# coaster.net
KiCad netlist of a schematic drawn in Altium Designer
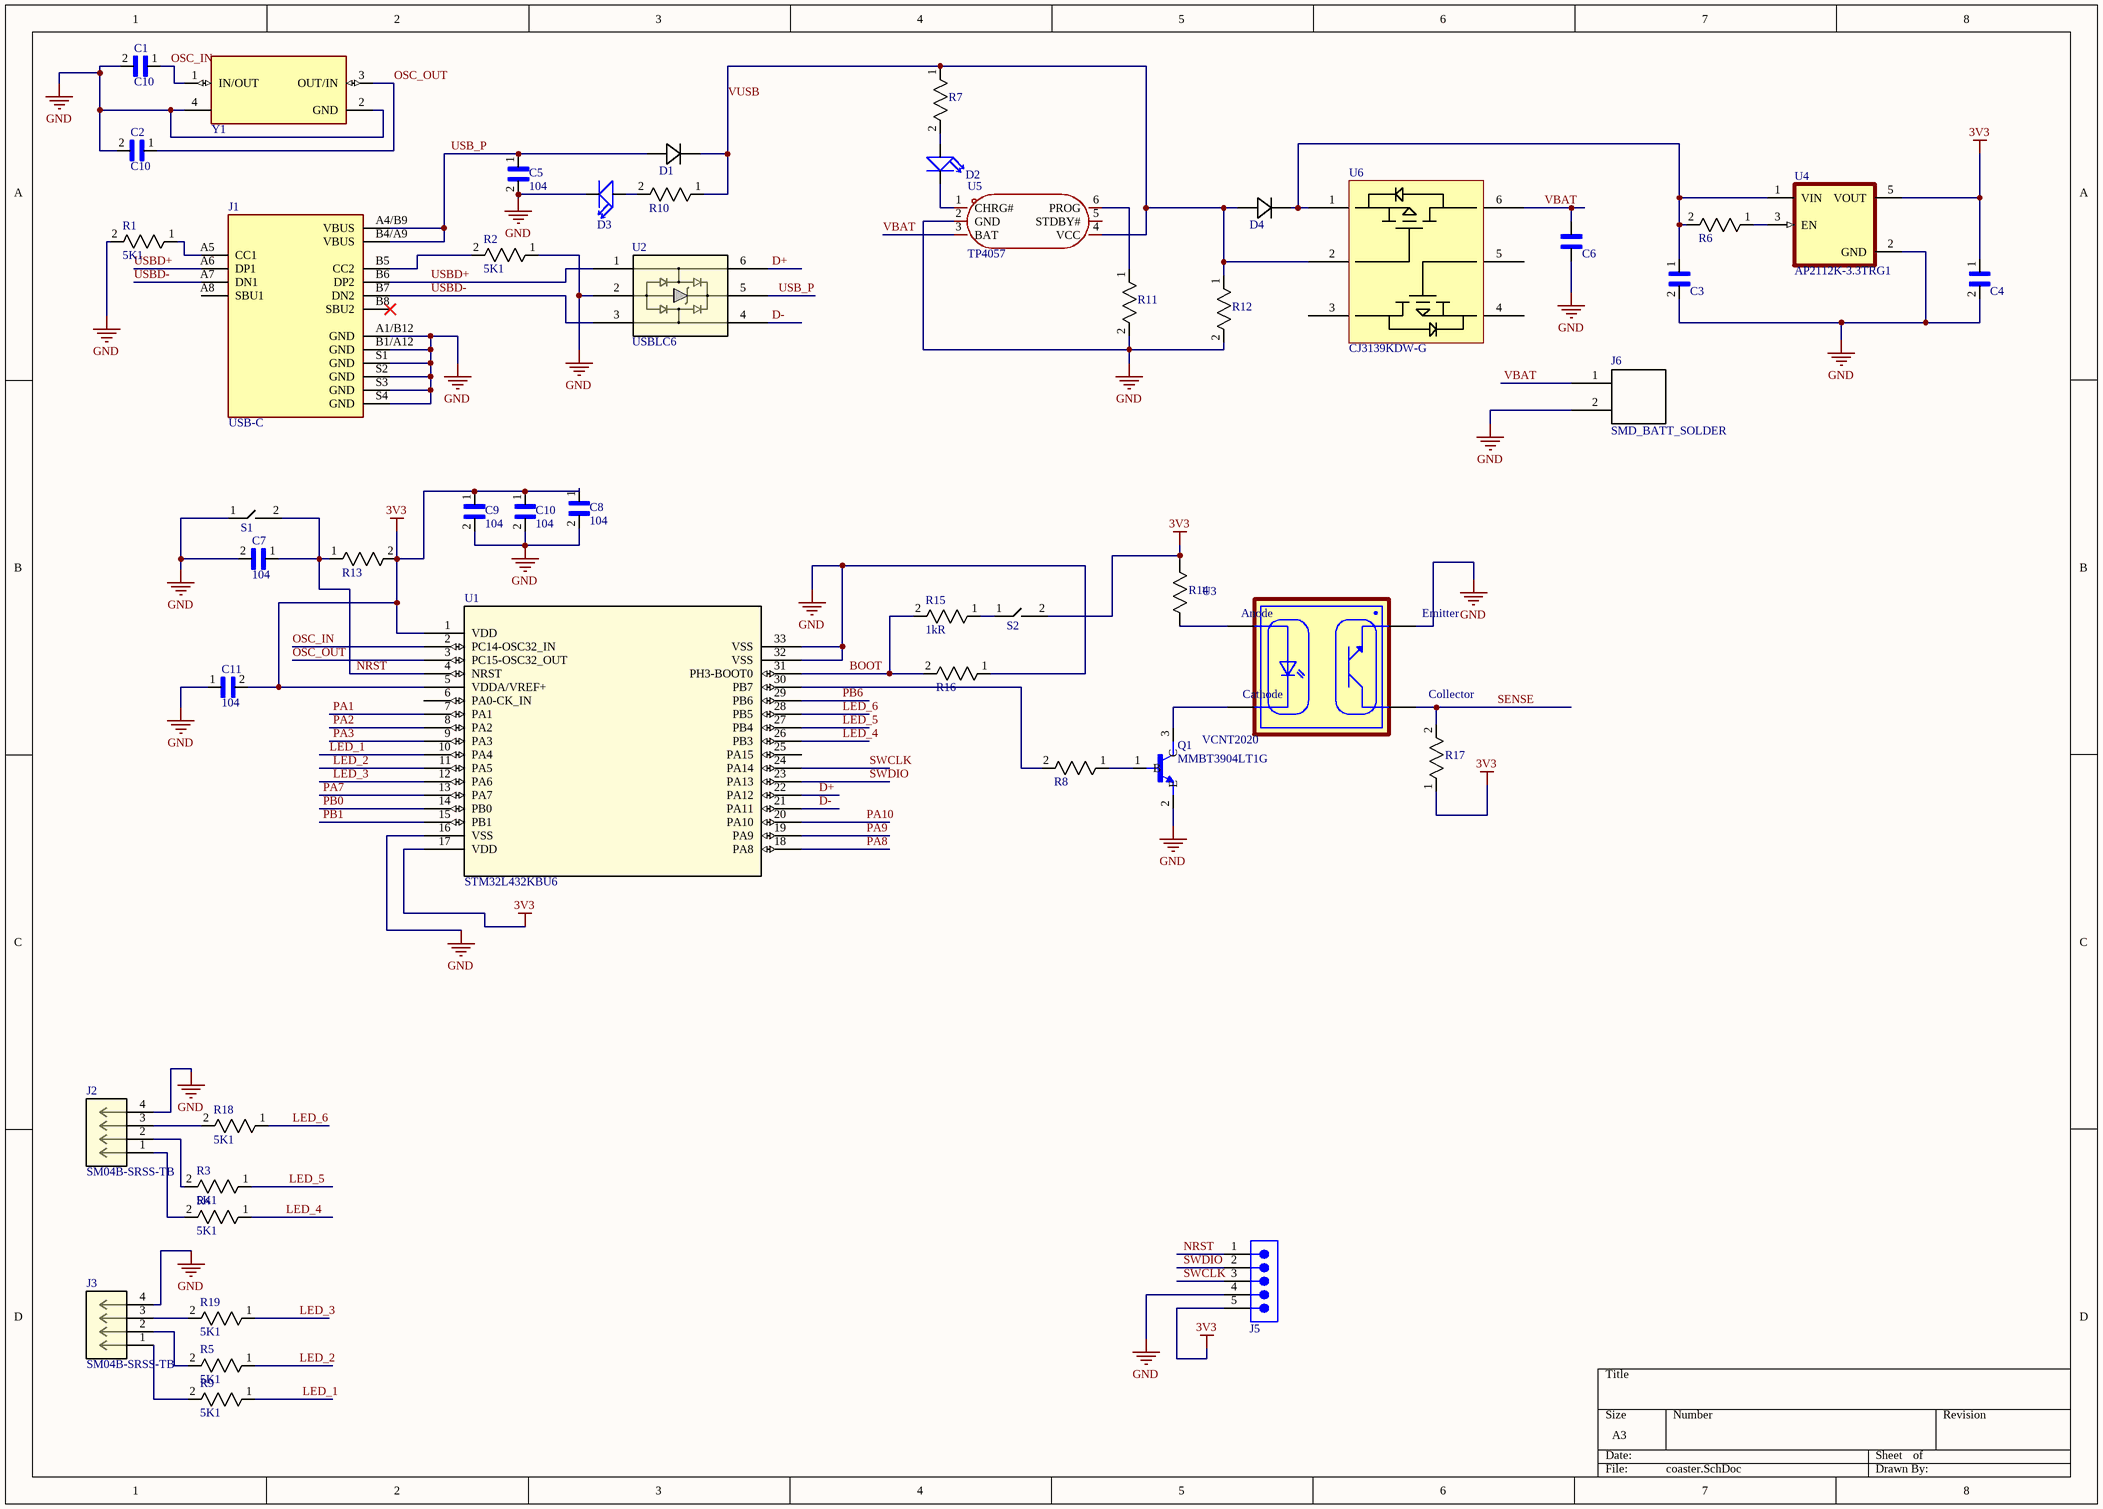
[diagram p0: coaster.SchDoc]

(export (version "E")
  (design (tool "Eeschema 10.0.6"))
  (components
    (comp (ref "C1")
      (value "C10")
      (footprint "RC0402")
      (description "0402 10 pF 50 V ±5 % Tolerance NP0 SMT Multilayer Ceramic Capacitor")
      (fields
        (field (name "MANUFACTURER") "Yageo")
        (field (name "MANUFACTURER PART NUMBER") "CC0402JRNPO9BN100")
      )
      (libsource (lib "Passive") (part "C10"))
    )
    (comp (ref "C2")
      (value "C10")
      (footprint "RC0402")
      (description "0402 10 pF 50 V ±5 % Tolerance NP0 SMT Multilayer Ceramic Capacitor")
      (fields
        (field (name "MANUFACTURER") "Yageo")
        (field (name "MANUFACTURER PART NUMBER") "CC0402JRNPO9BN100")
      )
      (libsource (lib "Passive") (part "C10"))
    )
    (comp (ref "C3")
      (value "CC0402KRX5R5BB105")
      (footprint "RC0402")
      (description "Multilayer Ceramic Capacitor, 1 uF, 100 V, ï¿½ 10%, X7R, 0402 [1005 Metric]")
      (fields (field (name "MANUFACTURER") "Yageo") (field (name "TOLERANCE") "10%"))
      (libsource (lib "imx8mnano") (part "C105"))
    )
    (comp (ref "C4")
      (value "CC0402KRX5R5BB105")
      (footprint "RC0402")
      (description "Multilayer Ceramic Capacitor, 1 uF, 100 V, ï¿½ 10%, X7R, 0402 [1005 Metric]")
      (fields (field (name "MANUFACTURER") "Yageo") (field (name "TOLERANCE") "10%"))
      (libsource (lib "imx8mnano") (part "C105"))
    )
    (comp (ref "C5")
      (value "104")
      (footprint "CAPC1005X55N2")
      (description "Multilayer Ceramic Capacitor, 0.1 uF, 16 V, ï¿½ 10%, X7R, 0402 [1005 Metric]")
      (fields
        (field (name "MANUFACTURER") "Yageo")
        (field (name "MANUFACTURER PART NUMBER") "CC0402KRX7R7BB104")
      )
      (libsource (lib "") (part "CC0402KRX7R7BB104_1"))
    )
    (comp (ref "C6")
      (value "CL21A106KOQNNNG")
      (footprint "CAPC2012X140N")
      (description "10 ÂµF Â±10% 16V Ceramic Capacitor X5R 0805 (2012 Metric)")
      (fields (field (name "MF") "Samsung Electro-Mechanics"))
      (libsource (lib "Passive") (part "10uF16v0805"))
    )
    (comp (ref "C7")
      (value "104")
      (footprint "CAPC1005X55N2")
      (description "Multilayer Ceramic Capacitor, 0.1 uF, 16 V, ï¿½ 10%, X7R, 0402 [1005 Metric]")
      (fields
        (field (name "MANUFACTURER") "Yageo")
        (field (name "MANUFACTURER PART NUMBER") "CC0402KRX7R7BB104")
      )
      (libsource (lib "Passive") (part "CC0402KRX7R7BB104"))
    )
    (comp (ref "C8")
      (value "104")
      (footprint "CAPC1005X55N2")
      (description "Multilayer Ceramic Capacitor, 0.1 uF, 16 V, ï¿½ 10%, X7R, 0402 [1005 Metric]")
      (fields
        (field (name "MANUFACTURER") "Yageo")
        (field (name "MANUFACTURER PART NUMBER") "CC0402KRX7R7BB104")
      )
      (libsource (lib "") (part "CC0402KRX7R7BB104_1"))
    )
    (comp (ref "C9")
      (value "104")
      (footprint "CAPC1005X55N2")
      (description "Multilayer Ceramic Capacitor, 0.1 uF, 16 V, ï¿½ 10%, X7R, 0402 [1005 Metric]")
      (fields
        (field (name "MANUFACTURER") "Yageo")
        (field (name "MANUFACTURER PART NUMBER") "CC0402KRX7R7BB104")
      )
      (libsource (lib "") (part "CC0402KRX7R7BB104_1"))
    )
    (comp (ref "C10")
      (value "104")
      (footprint "CAPC1005X55N2")
      (description "Multilayer Ceramic Capacitor, 0.1 uF, 16 V, ï¿½ 10%, X7R, 0402 [1005 Metric]")
      (fields
        (field (name "MANUFACTURER") "Yageo")
        (field (name "MANUFACTURER PART NUMBER") "CC0402KRX7R7BB104")
      )
      (libsource (lib "") (part "CC0402KRX7R7BB104_1"))
    )
    (comp (ref "C11")
      (value "104")
      (footprint "CAPC1005X55N2")
      (description "Multilayer Ceramic Capacitor, 0.1 uF, 16 V, ï¿½ 10%, X7R, 0402 [1005 Metric]")
      (fields
        (field (name "MANUFACTURER") "Yageo")
        (field (name "MANUFACTURER PART NUMBER") "CC0402KRX7R7BB104")
      )
      (libsource (lib "") (part "CC0402KRX7R7BB104_2"))
    )
    (comp (ref "D1")
      (value "SD103AWS-E3-08")
      (footprint "CR_WS-E3-08_VIS-L")
      (description "SCHOTTKY DIODE SOD323")
      (fields (field (name "COPYRIGHT") "Copyright (C) 2025 Ultra Librarian. All rights reserved."))
      (libsource (lib "Passive") (part "SD103AWS-E3-08"))
    )
    (comp (ref "D2")
      (value "LED")
      (footprint "LEDM1608X80")
      (description "Single Color LED, Ultra Bright Orange, Water Clear, 1.1mm")
      (fields
        (field (name "MANUFACTURER") "Vishay Lite-On")
        (field (name "MANUFACTURER PART NUMBER") "LTST-C190KFKT")
      )
      (libsource (lib "Passive") (part "LTST-C190KFKT"))
    )
    (comp (ref "D3")
      (value "LED")
      (footprint "LEDM1608X80")
      (description "Single Color LED, Ultra Bright Orange, Water Clear, 1.1mm")
      (fields
        (field (name "MANUFACTURER") "Vishay Lite-On")
        (field (name "MANUFACTURER PART NUMBER") "LTST-C190KFKT")
      )
      (libsource (lib "Passive") (part "LTST-C190KFKT"))
    )
    (comp (ref "D4")
      (value "SD103AWS-E3-08")
      (footprint "CR_WS-E3-08_VIS-L")
      (description "SCHOTTKY DIODE SOD323")
      (fields (field (name "COPYRIGHT") "Copyright (C) 2025 Ultra Librarian. All rights reserved."))
      (libsource (lib "Passive") (part "SD103AWS-E3-08"))
    )
    (comp (ref "J1")
      (value "USB-C")
      (footprint "GCT_USB4110GFA")
      (description "C42400246")
      (fields (field (name "MANUFACTURER") "HOAUC"))
      (libsource (lib "imx8mnano") (part "USB4110-GF-A"))
    )
    (comp (ref "J2")
      (value "SM04B-SRSS-TB")
      (footprint "CONN_SM04B-SRSS-TB_JST")
      (description "No Description Available")
      (fields (field (name "COPYRIGHT") "Copyright (C) 2025 Ultra Librarian. All rights reserved."))
      (libsource (lib "Connectors") (part "SM04B-SRSS-TB"))
    )
    (comp (ref "J3")
      (value "SM04B-SRSS-TB")
      (footprint "CONN_SM04B-SRSS-TB_JST")
      (description "No Description Available")
      (fields (field (name "COPYRIGHT") "Copyright (C) 2025 Ultra Librarian. All rights reserved."))
      (libsource (lib "Connectors") (part "SM04B-SRSS-TB"))
    )
    (comp (ref "J5")
      (value "61300511121")
      (footprint "HEADER_M_5")
      (description "THT Vertical Pin Header WR-PHD, Pitch 2.54 mm, Single Row, 5 pins")
      (fields (field (name "MANUFACTURER") "Wurth Electronics"))
      (libsource (lib "Connectors") (part "HEADER_M_5"))
    )
    (comp (ref "J6")
      (value "SMD_BATT_SOLDER")
      (footprint "SMD_BATT_SOLDER")
      (libsource (lib "Connectors") (part "SMD_BATT_SOLDER"))
    )
    (comp (ref "Q1")
      (value "MMBT3904LT1G")
      (footprint "SOT95P240X111-3N")
      (fields (field (name "MF") "ON Semiconductor"))
      (libsource (lib "Passive") (part "MMBT3904LT1G"))
    )
    (comp (ref "R1")
      (value "5K1")
      (footprint "RC0402")
      (description "SMD Chip Resistor, 5.1 kOhm, ï¿½ 1%, 62.5 mW, 0402 [1005 Metric], Thick Film, General Purpose")
      (fields
        (field (name "MANUFACTURER") "Yageo")
        (field (name "MANUFACTURER PART NUMBER") "RC0402FR-075K1L")
      )
      (libsource (lib "Passive") (part "RC0402FR-075K1L"))
    )
    (comp (ref "R2")
      (value "5K1")
      (footprint "RC0402")
      (description "SMD Chip Resistor, 5.1 kOhm, ï¿½ 1%, 62.5 mW, 0402 [1005 Metric], Thick Film, General Purpose")
      (fields
        (field (name "MANUFACTURER") "Yageo")
        (field (name "MANUFACTURER PART NUMBER") "RC0402FR-075K1L")
      )
      (libsource (lib "Passive") (part "RC0402FR-075K1L"))
    )
    (comp (ref "R3")
      (value "5K1")
      (footprint "RC0402")
      (description "SMD Chip Resistor, 5.1 kOhm, ï¿½ 1%, 62.5 mW, 0402 [1005 Metric], Thick Film, General Purpose")
      (fields
        (field (name "MANUFACTURER") "Yageo")
        (field (name "MANUFACTURER PART NUMBER") "RC0402FR-075K1L")
      )
      (libsource (lib "Passive") (part "RC0402FR-075K1L"))
    )
    (comp (ref "R4")
      (value "5K1")
      (footprint "RC0402")
      (description "SMD Chip Resistor, 5.1 kOhm, ï¿½ 1%, 62.5 mW, 0402 [1005 Metric], Thick Film, General Purpose")
      (fields
        (field (name "MANUFACTURER") "Yageo")
        (field (name "MANUFACTURER PART NUMBER") "RC0402FR-075K1L")
      )
      (libsource (lib "Passive") (part "RC0402FR-075K1L"))
    )
    (comp (ref "R5")
      (value "5K1")
      (footprint "RC0402")
      (description "SMD Chip Resistor, 5.1 kOhm, ï¿½ 1%, 62.5 mW, 0402 [1005 Metric], Thick Film, General Purpose")
      (fields
        (field (name "MANUFACTURER") "Yageo")
        (field (name "MANUFACTURER PART NUMBER") "RC0402FR-075K1L")
      )
      (libsource (lib "Passive") (part "RC0402FR-075K1L"))
    )
    (comp (ref "R6")
      (value "15K0402")
      (footprint "RC0402X")
      (description "Res Thin Film 0402 15K Ohm 0.1% 0.063W(1/16W) ±25ppm/C Pad SMD T/R")
      (fields
        (field (name "MANUFACTURER") "Yageo")
        (field (name "MANUFACTURER PART NUMBER") "RT0402BRD0715KL")
      )
      (libsource (lib "Passive") (part "15K0402"))
    )
    (comp (ref "R7")
      (value "ERA-2AEB332X")
      (footprint "RC0402")
      (description "Res Thin Film 0402 3.3K Ohm 0.1% 0.063W ±25ppm/°C Molded SMD Punched Carrier T/R")
      (fields (field (name "MANUFACTURER") "Panasonic") (field (name "TOLERANCE") "0.1%"))
      (libsource (lib "Passive") (part "3.3K402"))
    )
    (comp (ref "R8")
      (value "15K0402")
      (footprint "RC0402X")
      (description "Res Thin Film 0402 15K Ohm 0.1% 0.063W(1/16W) ±25ppm/C Pad SMD T/R")
      (fields
        (field (name "MANUFACTURER") "Yageo")
        (field (name "MANUFACTURER PART NUMBER") "RT0402BRD0715KL")
      )
      (libsource (lib "Passive") (part "15K0402"))
    )
    (comp (ref "R9")
      (value "5K1")
      (footprint "RC0402")
      (description "SMD Chip Resistor, 5.1 kOhm, ï¿½ 1%, 62.5 mW, 0402 [1005 Metric], Thick Film, General Purpose")
      (fields
        (field (name "MANUFACTURER") "Yageo")
        (field (name "MANUFACTURER PART NUMBER") "RC0402FR-075K1L")
      )
      (libsource (lib "Passive") (part "RC0402FR-075K1L"))
    )
    (comp (ref "R10")
      (value "ERA-2AEB332X")
      (footprint "RC0402")
      (description "Res Thin Film 0402 3.3K Ohm 0.1% 0.063W ±25ppm/°C Molded SMD Punched Carrier T/R")
      (fields (field (name "MANUFACTURER") "Panasonic") (field (name "TOLERANCE") "0.1%"))
      (libsource (lib "Passive") (part "3.3K402"))
    )
    (comp (ref "R11")
      (value "RC0402JR-0710KL")
      (footprint "RC0402X")
      (description "SMD Chip Resistor, 10 Kohm, ½ 5%, 62.5 Mw, 0402 [1005 Metric], Thick Film, General Purpose")
      (fields (field (name "MANUFACTURER") "Yageo") (field (name "TOLERANCE") "5%"))
      (libsource (lib "Passive") (part "10K0402"))
    )
    (comp (ref "R12")
      (value "RC0402JR-07100KL")
      (footprint "RC0402X")
      (description "SMD Chip Resistor, 100 Kohm, ½ 5%, 62.5 Mw, 0402 [1005 Metric], Thick Film, General Purpose")
      (fields (field (name "MANUFACTURER") "Yageo") (field (name "TOLERANCE") "5%"))
      (libsource (lib "Passive") (part "100K0402"))
    )
    (comp (ref "R13")
      (value "RC0402JR-0710KL")
      (footprint "RC0402X")
      (description "SMD Chip Resistor, 10 Kohm, ½ 5%, 62.5 Mw, 0402 [1005 Metric], Thick Film, General Purpose")
      (fields (field (name "MANUFACTURER") "Yageo") (field (name "TOLERANCE") "5%"))
      (libsource (lib "Passive") (part "10K0402"))
    )
    (comp (ref "R14")
      (value "CRGCQ1206F2K2")
      (footprint "STA_RMCF1206_STP-L")
      (description "SMD Chip Resistor, 2.2 kOhm, ± 1%, 250 mW, 1206 [3216 Metric], Thick Film, General Purpose")
      (fields (field (name "MANUFACTURER") "TE Connectivity"))
      (libsource (lib "Passive") (part "R1206F2K2"))
    )
    (comp (ref "R15")
      (value "RC0402JR-071KL")
      (footprint "RC0402X")
      (description "SMD Chip Resistor, 1 Kohm, ½ 5%, 63 Mw, 0402 [1005 Metric], Thick Film, General Purpose")
      (fields
        (field (name "MANUFACTURER") "Yageo")
        (field (name "TOLERANCE") "5%")
        (field (name "RESISTANCE") "1kR")
      )
      (libsource (lib "Passive") (part "1K0402"))
    )
    (comp (ref "R16")
      (value "RC0402JR-07100KL")
      (footprint "RC0402X")
      (description "SMD Chip Resistor, 100 Kohm, ½ 5%, 62.5 Mw, 0402 [1005 Metric], Thick Film, General Purpose")
      (fields (field (name "MANUFACTURER") "Yageo") (field (name "TOLERANCE") "5%"))
      (libsource (lib "Passive") (part "100K0402"))
    )
    (comp (ref "R17")
      (value "RC0402JR-0710KL")
      (footprint "RC0402X")
      (description "SMD Chip Resistor, 10 Kohm, ½ 5%, 62.5 Mw, 0402 [1005 Metric], Thick Film, General Purpose")
      (fields (field (name "MANUFACTURER") "Yageo") (field (name "TOLERANCE") "5%"))
      (libsource (lib "Passive") (part "10K0402"))
    )
    (comp (ref "R18")
      (value "5K1")
      (footprint "RC0402")
      (description "SMD Chip Resistor, 5.1 kOhm, ï¿½ 1%, 62.5 mW, 0402 [1005 Metric], Thick Film, General Purpose")
      (fields
        (field (name "MANUFACTURER") "Yageo")
        (field (name "MANUFACTURER PART NUMBER") "RC0402FR-075K1L")
      )
      (libsource (lib "Passive") (part "RC0402FR-075K1L"))
    )
    (comp (ref "R19")
      (value "5K1")
      (footprint "RC0402")
      (description "SMD Chip Resistor, 5.1 kOhm, ï¿½ 1%, 62.5 mW, 0402 [1005 Metric], Thick Film, General Purpose")
      (fields
        (field (name "MANUFACTURER") "Yageo")
        (field (name "MANUFACTURER PART NUMBER") "RC0402FR-075K1L")
      )
      (libsource (lib "Passive") (part "RC0402FR-075K1L"))
    )
    (comp (ref "S1")
      (value "SW_P")
      (footprint "SW")
      (description "Switch Tactile N.O. SPST Round Button Gull Wing 0.05A 12VDC 0.98N SMD T/R")
      (fields
        (field (name "MANUFACTURER") "Alps Electric")
        (field (name "MANUFACTURER PART NUMBER") "SKRKAHE020")
      )
      (libsource (lib "imx8mnano") (part "SW_P"))
    )
    (comp (ref "S2")
      (value "SW_P")
      (footprint "SW")
      (description "Switch Tactile N.O. SPST Round Button Gull Wing 0.05A 12VDC 0.98N SMD T/R")
      (fields
        (field (name "MANUFACTURER") "Alps Electric")
        (field (name "MANUFACTURER PART NUMBER") "SKRKAHE020")
      )
      (libsource (lib "imx8mnano") (part "SW_P"))
    )
    (comp (ref "U1")
      (value "STM32L432KBU6")
      (footprint "UFQFPN-32")
      (description "Ultra-low-power with FPU ARM Cortex-M4 MCU 80 MHz with 128 Kbytes Flash, USB")
      (fields (field (name "MANUFACTURER") "STMicroelectronics"))
      (libsource (lib "Microcontrollers") (part "STM32L432KBU6"))
    )
    (comp (ref "U2")
      (value "USBLC6")
      (footprint "SOT23-6L_STM")
      (description "ESD Suppressor Diode Array Dual Uni-Dir 15kV Air Gap/15kV Contact Disc 6-Pin SOT-23 T/R")
      (fields
        (field (name "MANUFACTURER") "STMicroelectronics")
        (field (name "MANUFACTURER PART NUMBER") "USBLC6-2SC6")
      )
      (libsource (lib "Passive") (part "USBLC6-2SC6"))
    )
    (comp (ref "U3")
      (value "VCNT2020")
      (footprint "XDCR_VCNT2020")
      (description "Reflective Optical Sensor 0.02 (0.5mm) 4-SMD Module")
      (fields (field (name "MF") "Vishay"))
      (libsource (lib "Passive") (part "VCNT2020"))
    )
    (comp (ref "U4")
      (value "AP2112K-3.3TRG1")
      (footprint "SOT95P285X140-5N")
      (description "Linear Voltage Regulator IC Positive Fixed 1 Output 600mA SOT-25")
      (fields (field (name "MF") "Diodes Inc."))
      (libsource (lib "Passive") (part "AP2112K-3.3TRG1"))
    )
    (comp (ref "U5")
      (value "TP4057")
      (footprint "SOP65P210X110-6N")
      (description "6.5V /Polymer 1 500mA SOT-23-6 Battery Management ICs ROHS")
      (fields (field (name "MANUFACTURER") "UMW(Youtai Semiconductor)"))
      (libsource (lib "Passive") (part "TP4057"))
    )
    (comp (ref "U6")
      (value "CJ3139KDW-G")
      (footprint "SOP65P210X110-6N")
      (description "Trans Mosfet P-ch 20V 0.66A 6-PIN SOT-363 T/r")
      (fields (field (name "MANUFACTURER") "Comchip"))
      (libsource (lib "Passive") (part "CJ3139KDW-G"))
    )
    (comp (ref "Y1")
      (value "ECS-80-12-33-JGN-TR")
      (footprint "XTAL_ECS-240-8-33-AGN-TR")
      (description "Crystal 8MHz ±20ppm (Tol) ±30ppm (Stability) 12pF FUND 400Ohm 4-Pin Mini-CSMD T/R")
      (fields (field (name "MANUFACTURER") "ECS International"))
      (libsource (lib "Passive") (part "Crystal_8MHz_SMD"))
    )
  )
  (nets
    (net (code "1") (name "/BOOT") (class "Default")
      (node (ref "R15") (pin "2") (pinfunction "2_2") (pintype "passive"))
      (node (ref "R16") (pin "2") (pinfunction "2_2") (pintype "passive"))
      (node (ref "U1") (pin "31") (pinfunction "PH3-BOOT0_31") (pintype "bidirectional"))
    )
    (net (code "2") (name "/D+") (class "Default")
      (node (ref "U1") (pin "22") (pinfunction "PA12_22") (pintype "bidirectional"))
      (node (ref "U2") (pin "6") (pinfunction "6_6") (pintype "passive"))
    )
    (net (code "3") (name "/D-") (class "Default")
      (node (ref "U1") (pin "21") (pinfunction "PA11_21") (pintype "bidirectional"))
      (node (ref "U2") (pin "4") (pinfunction "4_4") (pintype "passive"))
    )
    (net (code "4") (name "/LED_1") (class "Default")
      (node (ref "R9") (pin "1") (pinfunction "1_1") (pintype "passive"))
      (node (ref "U1") (pin "10") (pinfunction "PA4_10") (pintype "bidirectional"))
    )
    (net (code "5") (name "/LED_2") (class "Default")
      (node (ref "R5") (pin "1") (pinfunction "1_1") (pintype "passive"))
      (node (ref "U1") (pin "11") (pinfunction "PA5_11") (pintype "bidirectional"))
    )
    (net (code "6") (name "/LED_3") (class "Default")
      (node (ref "R19") (pin "1") (pinfunction "1_1") (pintype "passive"))
      (node (ref "U1") (pin "12") (pinfunction "PA6_12") (pintype "bidirectional"))
    )
    (net (code "7") (name "/LED_4") (class "Default")
      (node (ref "R4") (pin "1") (pinfunction "1_1") (pintype "passive"))
      (node (ref "U1") (pin "26") (pinfunction "PB3_26") (pintype "bidirectional"))
    )
    (net (code "8") (name "/LED_5") (class "Default")
      (node (ref "R3") (pin "1") (pinfunction "1_1") (pintype "passive"))
      (node (ref "U1") (pin "27") (pinfunction "PB4_27") (pintype "bidirectional"))
    )
    (net (code "9") (name "/LED_6") (class "Default")
      (node (ref "R18") (pin "1") (pinfunction "1_1") (pintype "passive"))
      (node (ref "U1") (pin "28") (pinfunction "PB5_28") (pintype "bidirectional"))
    )
    (net (code "10") (name "/NRST") (class "Default")
      (node (ref "C7") (pin "1") (pinfunction "1_1") (pintype "passive"))
      (node (ref "J5") (pin "1") (pinfunction "1_1") (pintype "passive"))
      (node (ref "R13") (pin "1") (pinfunction "1_1") (pintype "passive"))
      (node (ref "S1") (pin "2") (pinfunction "2_2") (pintype "passive"))
      (node (ref "U1") (pin "4") (pinfunction "NRST_4") (pintype "bidirectional"))
    )
    (net (code "11") (name "/OSC_IN") (class "Default")
      (node (ref "C1") (pin "1") (pinfunction "1_1") (pintype "passive"))
      (node (ref "U1") (pin "2") (pinfunction "PC14-OSC32_IN_2") (pintype "bidirectional"))
      (node (ref "Y1") (pin "1") (pinfunction "IN/OUT_1") (pintype "bidirectional"))
    )
    (net (code "12") (name "/OSC_OUT") (class "Default")
      (node (ref "C2") (pin "1") (pinfunction "1_1") (pintype "passive"))
      (node (ref "U1") (pin "3") (pinfunction "PC15-OSC32_OUT_3") (pintype "bidirectional"))
      (node (ref "Y1") (pin "3") (pinfunction "OUT/IN_3") (pintype "bidirectional"))
    )
    (net (code "13") (name "/PA1") (class "Default")
      (node (ref "U1") (pin "7") (pinfunction "PA1_7") (pintype "bidirectional"))
    )
    (net (code "14") (name "/PA2") (class "Default")
      (node (ref "U1") (pin "8") (pinfunction "PA2_8") (pintype "bidirectional"))
    )
    (net (code "15") (name "/PA3") (class "Default")
      (node (ref "U1") (pin "9") (pinfunction "PA3_9") (pintype "bidirectional"))
    )
    (net (code "16") (name "/PA7") (class "Default")
      (node (ref "U1") (pin "13") (pinfunction "PA7_13") (pintype "bidirectional"))
    )
    (net (code "17") (name "/PA8") (class "Default")
      (node (ref "U1") (pin "18") (pinfunction "PA8_18") (pintype "bidirectional"))
    )
    (net (code "18") (name "/PA9") (class "Default")
      (node (ref "U1") (pin "19") (pinfunction "PA9_19") (pintype "bidirectional"))
    )
    (net (code "19") (name "/PA10") (class "Default")
      (node (ref "U1") (pin "20") (pinfunction "PA10_20") (pintype "bidirectional"))
    )
    (net (code "20") (name "/PB0") (class "Default")
      (node (ref "U1") (pin "14") (pinfunction "PB0_14") (pintype "bidirectional"))
    )
    (net (code "21") (name "/PB1") (class "Default")
      (node (ref "U1") (pin "15") (pinfunction "PB1_15") (pintype "bidirectional"))
    )
    (net (code "22") (name "/PB6") (class "Default")
      (node (ref "U1") (pin "29") (pinfunction "PB6_29") (pintype "bidirectional"))
    )
    (net (code "23") (name "/SENSE") (class "Default")
      (node (ref "R17") (pin "2") (pinfunction "2_2") (pintype "passive"))
      (node (ref "U3") (pin "2") (pinfunction "COLLECTOR_2") (pintype "passive"))
    )
    (net (code "24") (name "/SWCLK") (class "Default")
      (node (ref "J5") (pin "3") (pinfunction "3_3") (pintype "passive"))
      (node (ref "U1") (pin "24") (pinfunction "PA14_24") (pintype "bidirectional"))
    )
    (net (code "25") (name "/SWDIO") (class "Default")
      (node (ref "J5") (pin "2") (pinfunction "2_2") (pintype "passive"))
      (node (ref "U1") (pin "23") (pinfunction "PA13_23") (pintype "bidirectional"))
    )
    (net (code "26") (name "/USBD+") (class "Default")
      (node (ref "J1") (pin "A6") (pinfunction "DP1_A6") (pintype "passive"))
      (node (ref "J1") (pin "B6") (pinfunction "DP2_B6") (pintype "passive"))
      (node (ref "U2") (pin "1") (pinfunction "1_1") (pintype "passive"))
    )
    (net (code "27") (name "/USBD-") (class "Default")
      (node (ref "J1") (pin "A7") (pinfunction "DN1_A7") (pintype "passive"))
      (node (ref "J1") (pin "B7") (pinfunction "DN2_B7") (pintype "passive"))
      (node (ref "U2") (pin "3") (pinfunction "3_3") (pintype "passive"))
    )
    (net (code "28") (name "/USB_P") (class "Default")
      (node (ref "C5") (pin "1") (pinfunction "1_1") (pintype "passive"))
      (node (ref "D1") (pin "2") (pinfunction "2_2") (pintype "passive"))
      (node (ref "J1") (pin "A4/B9") (pinfunction "VBUS_A4/B9") (pintype "passive"))
      (node (ref "J1") (pin "B4/A9") (pinfunction "VBUS_B4/A9") (pintype "passive"))
      (node (ref "U2") (pin "5") (pinfunction "5_5") (pintype "passive"))
    )
    (net (code "29") (name "/VBAT") (class "Default")
      (node (ref "C6") (pin "2") (pinfunction "2_2") (pintype "passive"))
      (node (ref "J6") (pin "1") (pinfunction "1_1") (pintype "passive"))
      (node (ref "U5") (pin "3") (pinfunction "BAT_3") (pintype "passive"))
      (node (ref "U6") (pin "6") (pinfunction "6_6") (pintype "passive"))
    )
    (net (code "30") (name "/VUSB") (class "Default")
      (node (ref "D1") (pin "1") (pinfunction "1_1") (pintype "passive"))
      (node (ref "D4") (pin "2") (pinfunction "2_2") (pintype "passive"))
      (node (ref "R10") (pin "1") (pinfunction "1_1") (pintype "passive"))
      (node (ref "R12") (pin "1") (pinfunction "1_1") (pintype "passive"))
      (node (ref "R7") (pin "1") (pinfunction "1_1") (pintype "passive"))
      (node (ref "U5") (pin "4") (pinfunction "VCC_4") (pintype "passive"))
      (node (ref "U6") (pin "2") (pinfunction "2_2") (pintype "passive"))
    )
    (net (code "31") (name "3V3") (class "Default")
      (node (ref "C10") (pin "1") (pinfunction "1_1") (pintype "passive"))
      (node (ref "C11") (pin "2") (pinfunction "2_2") (pintype "passive"))
      (node (ref "C4") (pin "1") (pinfunction "1_1") (pintype "passive"))
      (node (ref "C8") (pin "1") (pinfunction "1_1") (pintype "passive"))
      (node (ref "C9") (pin "1") (pinfunction "1_1") (pintype "passive"))
      (node (ref "J5") (pin "5") (pinfunction "5_5") (pintype "passive"))
      (node (ref "R13") (pin "2") (pinfunction "2_2") (pintype "passive"))
      (node (ref "R14") (pin "2") (pinfunction "2_2") (pintype "passive"))
      (node (ref "R17") (pin "1") (pinfunction "1_1") (pintype "passive"))
      (node (ref "S2") (pin "2") (pinfunction "2_2") (pintype "passive"))
      (node (ref "U1") (pin "1") (pinfunction "VDD_1") (pintype "power_in"))
      (node (ref "U1") (pin "17") (pinfunction "VDD_17") (pintype "power_in"))
      (node (ref "U1") (pin "5") (pinfunction "VDDA/VREF+_5") (pintype "power_in"))
      (node (ref "U4") (pin "5") (pinfunction "VOUT_5") (pintype "power_in"))
    )
    (net (code "32") (name "GND") (class "Default")
      (node (ref "C1") (pin "2") (pinfunction "2_2") (pintype "passive"))
      (node (ref "C10") (pin "2") (pinfunction "2_2") (pintype "passive"))
      (node (ref "C11") (pin "1") (pinfunction "1_1") (pintype "passive"))
      (node (ref "C2") (pin "2") (pinfunction "2_2") (pintype "passive"))
      (node (ref "C3") (pin "2") (pinfunction "2_2") (pintype "passive"))
      (node (ref "C4") (pin "2") (pinfunction "2_2") (pintype "passive"))
      (node (ref "C5") (pin "2") (pinfunction "2_2") (pintype "passive"))
      (node (ref "C6") (pin "1") (pinfunction "1_1") (pintype "passive"))
      (node (ref "C7") (pin "2") (pinfunction "2_2") (pintype "passive"))
      (node (ref "C8") (pin "2") (pinfunction "2_2") (pintype "passive"))
      (node (ref "C9") (pin "2") (pinfunction "2_2") (pintype "passive"))
      (node (ref "D3") (pin "C") (pinfunction "C_C") (pintype "passive"))
      (node (ref "J1") (pin "A1/B12") (pinfunction "GND_A1/B12") (pintype "passive"))
      (node (ref "J1") (pin "B1/A12") (pinfunction "GND_B1/A12") (pintype "passive"))
      (node (ref "J1") (pin "S1") (pinfunction "GND_S1") (pintype "passive"))
      (node (ref "J1") (pin "S2") (pinfunction "GND_S2") (pintype "passive"))
      (node (ref "J1") (pin "S3") (pinfunction "GND_S3") (pintype "passive"))
      (node (ref "J1") (pin "S4") (pinfunction "GND_S4") (pintype "passive"))
      (node (ref "J2") (pin "4") (pinfunction "4_4") (pintype "passive"))
      (node (ref "J3") (pin "4") (pinfunction "4_4") (pintype "passive"))
      (node (ref "J5") (pin "4") (pinfunction "4_4") (pintype "passive"))
      (node (ref "J6") (pin "2") (pinfunction "2_2") (pintype "passive"))
      (node (ref "Q1") (pin "2") (pinfunction "E_2") (pintype "passive"))
      (node (ref "R1") (pin "2") (pinfunction "2_2") (pintype "passive"))
      (node (ref "R11") (pin "2") (pinfunction "2_2") (pintype "passive"))
      (node (ref "R12") (pin "2") (pinfunction "2_2") (pintype "passive"))
      (node (ref "R16") (pin "1") (pinfunction "1_1") (pintype "passive"))
      (node (ref "R2") (pin "1") (pinfunction "1_1") (pintype "passive"))
      (node (ref "S1") (pin "1") (pinfunction "1_1") (pintype "passive"))
      (node (ref "U1") (pin "16") (pinfunction "VSS_16") (pintype "power_in"))
      (node (ref "U1") (pin "32") (pinfunction "VSS_32") (pintype "power_in"))
      (node (ref "U1") (pin "33") (pinfunction "VSS_33") (pintype "power_in"))
      (node (ref "U2") (pin "2") (pinfunction "2_2") (pintype "passive"))
      (node (ref "U3") (pin "1") (pinfunction "EMITTER_1") (pintype "passive"))
      (node (ref "U4") (pin "2") (pinfunction "GND_2") (pintype "power_in"))
      (node (ref "U5") (pin "2") (pinfunction "GND_2") (pintype "passive"))
      (node (ref "Y1") (pin "2") (pinfunction "GND_2") (pintype "power_in"))
      (node (ref "Y1") (pin "4") (pinfunction "GND_4") (pintype "power_in"))
    )
    (net (code "33") (name "Net-(D2-PadA)") (class "Default")
      (node (ref "D2") (pin "A") (pinfunction "A_A") (pintype "passive"))
      (node (ref "R7") (pin "2") (pinfunction "2_2") (pintype "passive"))
    )
    (net (code "34") (name "Net-(D3-PadA)") (class "Default")
      (node (ref "D3") (pin "A") (pinfunction "A_A") (pintype "passive"))
      (node (ref "R10") (pin "2") (pinfunction "2_2") (pintype "passive"))
    )
    (net (code "35") (name "Net-(J1-CC1)") (class "Default")
      (node (ref "J1") (pin "A5") (pinfunction "CC1_A5") (pintype "passive"))
      (node (ref "R1") (pin "1") (pinfunction "1_1") (pintype "passive"))
    )
    (net (code "36") (name "Net-(J1-CC2)") (class "Default")
      (node (ref "J1") (pin "B5") (pinfunction "CC2_B5") (pintype "passive"))
      (node (ref "R2") (pin "2") (pinfunction "2_2") (pintype "passive"))
    )
    (net (code "37") (name "Net-(J2-Pad1)") (class "Default")
      (node (ref "J2") (pin "1") (pinfunction "1_1") (pintype "passive"))
      (node (ref "R4") (pin "2") (pinfunction "2_2") (pintype "passive"))
    )
    (net (code "38") (name "Net-(J2-Pad2)") (class "Default")
      (node (ref "J2") (pin "2") (pinfunction "2_2") (pintype "passive"))
      (node (ref "R3") (pin "2") (pinfunction "2_2") (pintype "passive"))
    )
    (net (code "39") (name "Net-(J2-Pad3)") (class "Default")
      (node (ref "J2") (pin "3") (pinfunction "3_3") (pintype "passive"))
      (node (ref "R18") (pin "2") (pinfunction "2_2") (pintype "passive"))
    )
    (net (code "40") (name "Net-(J3-Pad1)") (class "Default")
      (node (ref "J3") (pin "1") (pinfunction "1_1") (pintype "passive"))
      (node (ref "R9") (pin "2") (pinfunction "2_2") (pintype "passive"))
    )
    (net (code "41") (name "Net-(J3-Pad2)") (class "Default")
      (node (ref "J3") (pin "2") (pinfunction "2_2") (pintype "passive"))
      (node (ref "R5") (pin "2") (pinfunction "2_2") (pintype "passive"))
    )
    (net (code "42") (name "Net-(J3-Pad3)") (class "Default")
      (node (ref "J3") (pin "3") (pinfunction "3_3") (pintype "passive"))
      (node (ref "R19") (pin "2") (pinfunction "2_2") (pintype "passive"))
    )
    (net (code "43") (name "Net-(Q1-B)") (class "Default")
      (node (ref "Q1") (pin "1") (pinfunction "B_1") (pintype "passive"))
      (node (ref "R8") (pin "1") (pinfunction "1_1") (pintype "passive"))
    )
    (net (code "44") (name "Net-(Q1-C)") (class "Default")
      (node (ref "Q1") (pin "3") (pinfunction "C_3") (pintype "passive"))
      (node (ref "U3") (pin "4") (pinfunction "CATHODE_4") (pintype "passive"))
    )
    (net (code "45") (name "Net-(R15-Pad1)") (class "Default")
      (node (ref "R15") (pin "1") (pinfunction "1_1") (pintype "passive"))
      (node (ref "S2") (pin "1") (pinfunction "1_1") (pintype "passive"))
    )
    (net (code "46") (name "Net-(U1-PB7)") (class "Default")
      (node (ref "R8") (pin "2") (pinfunction "2_2") (pintype "passive"))
      (node (ref "U1") (pin "30") (pinfunction "PB7_30") (pintype "bidirectional"))
    )
    (net (code "47") (name "Net-(U3-ANODE)") (class "Default")
      (node (ref "R14") (pin "1") (pinfunction "1_1") (pintype "passive"))
      (node (ref "U3") (pin "3") (pinfunction "ANODE_3") (pintype "passive"))
    )
    (net (code "48") (name "Net-(U4-EN)") (class "Default")
      (node (ref "R6") (pin "1") (pinfunction "1_1") (pintype "passive"))
      (node (ref "U4") (pin "3") (pinfunction "EN_3") (pintype "input"))
    )
    (net (code "49") (name "Net-(U4-VIN)") (class "Default")
      (node (ref "C3") (pin "1") (pinfunction "1_1") (pintype "passive"))
      (node (ref "D4") (pin "1") (pinfunction "1_1") (pintype "passive"))
      (node (ref "R6") (pin "2") (pinfunction "2_2") (pintype "passive"))
      (node (ref "U4") (pin "1") (pinfunction "VIN_1") (pintype "power_in"))
      (node (ref "U6") (pin "1") (pinfunction "1_1") (pintype "passive"))
    )
    (net (code "50") (name "Net-(U5-CHRG#)") (class "Default")
      (node (ref "D2") (pin "C") (pinfunction "C_C") (pintype "passive"))
      (node (ref "U5") (pin "1") (pinfunction "CHRG#_1") (pintype "passive"))
    )
    (net (code "51") (name "Net-(U5-PROG)") (class "Default")
      (node (ref "R11") (pin "1") (pinfunction "1_1") (pintype "passive"))
      (node (ref "U5") (pin "6") (pinfunction "PROG_6") (pintype "passive"))
    )
    (net (code "52") (name "unconnected-(J1-SBU1-PadA8)") (class "Default")
      (node (ref "J1") (pin "A8") (pinfunction "SBU1_A8") (pintype "passive"))
    )
    (net (code "53") (name "unconnected-(J1-SBU2-PadB8)") (class "Default")
      (node (ref "J1") (pin "B8") (pinfunction "SBU2_B8") (pintype "passive+no_connect"))
    )
    (net (code "54") (name "unconnected-(U1-PA0-CK_IN-Pad6)") (class "Default")
      (node (ref "U1") (pin "6") (pinfunction "PA0-CK_IN_6") (pintype "bidirectional"))
    )
    (net (code "55") (name "unconnected-(U1-PA15-Pad25)") (class "Default")
      (node (ref "U1") (pin "25") (pinfunction "PA15_25") (pintype "bidirectional"))
    )
    (net (code "56") (name "unconnected-(U5-STDBY#-Pad5)") (class "Default")
      (node (ref "U5") (pin "5") (pinfunction "STDBY#_5") (pintype "passive"))
    )
    (net (code "57") (name "unconnected-(U6-Pad3)") (class "Default")
      (node (ref "U6") (pin "3") (pinfunction "3_3") (pintype "passive"))
    )
    (net (code "58") (name "unconnected-(U6-Pad4)") (class "Default")
      (node (ref "U6") (pin "4") (pinfunction "4_4") (pintype "passive"))
    )
    (net (code "59") (name "unconnected-(U6-Pad5)") (class "Default")
      (node (ref "U6") (pin "5") (pinfunction "5_5") (pintype "passive"))
    )
  )
)
